# Button.net
KiCad netlist of a schematic drawn in Altium Designer
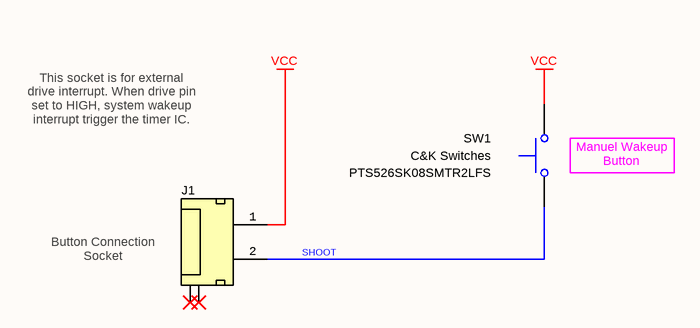
[diagram p0: Button.SchDoc]

(export (version "E")
  (design (tool "Eeschema 10.0.6"))
  (components
    (comp (ref "J1")
      (value "2P SMD Tunic Connector")
      (footprint "Connector_Tunic 2P")
      (description "Mini Tunic Connector with 2P")
      (fields
        (field (name "MANUFACTURER PART NUMBER") "53261-0271")
        (field (name "MOUSER PART NUMBER") "538-53261-0271")
      )
      (libsource (lib "Akkoyun") (part "Connector - Mini Tunic 2P (1.25)"))
    )
    (comp (ref "SW1")
      (value "PTS526SK08SMTR2LFS")
      (footprint "PTS526_Switch")
      (description "Switch Tactile N.O. SPST Flush Round Button Gull Wing 0.05A 12VDC 200000Cycles 2.45N SMD T/R")
      (fields
        (field (name "MANUFACTURER NAME") "C&K Switches")
        (field (name "MANUFACTURER PART NUMBER") "PTS526SK08SMTR2LFS")
      )
      (libsource (lib "Akkoyun") (part "Switch - Push Button"))
    )
  )
  (nets
    (net (code "1") (name "/SHOOT") (class "Default")
      (node (ref "J1") (pin "2") (pinfunction "Pin2_2") (pintype "passive"))
      (node (ref "SW1") (pin "1") (pinfunction "NC_1") (pintype "passive"))
    )
    (net (code "2") (name "VCC") (class "Default")
      (node (ref "J1") (pin "1") (pinfunction "Pin1_1") (pintype "passive"))
      (node (ref "SW1") (pin "2") (pinfunction "COM_2") (pintype "passive"))
    )
    (net (code "3") (name "unconnected-(J1-GND-Pad3)") (class "Default")
      (node (ref "J1") (pin "3") (pinfunction "GND_3") (pintype "passive+no_connect"))
    )
    (net (code "4") (name "unconnected-(J1-GND-Pad4)") (class "Default")
      (node (ref "J1") (pin "4") (pinfunction "GND_4") (pintype "passive+no_connect"))
    )
  )
)
